# Power.net
KiCad netlist of a schematic drawn in Altium Designer
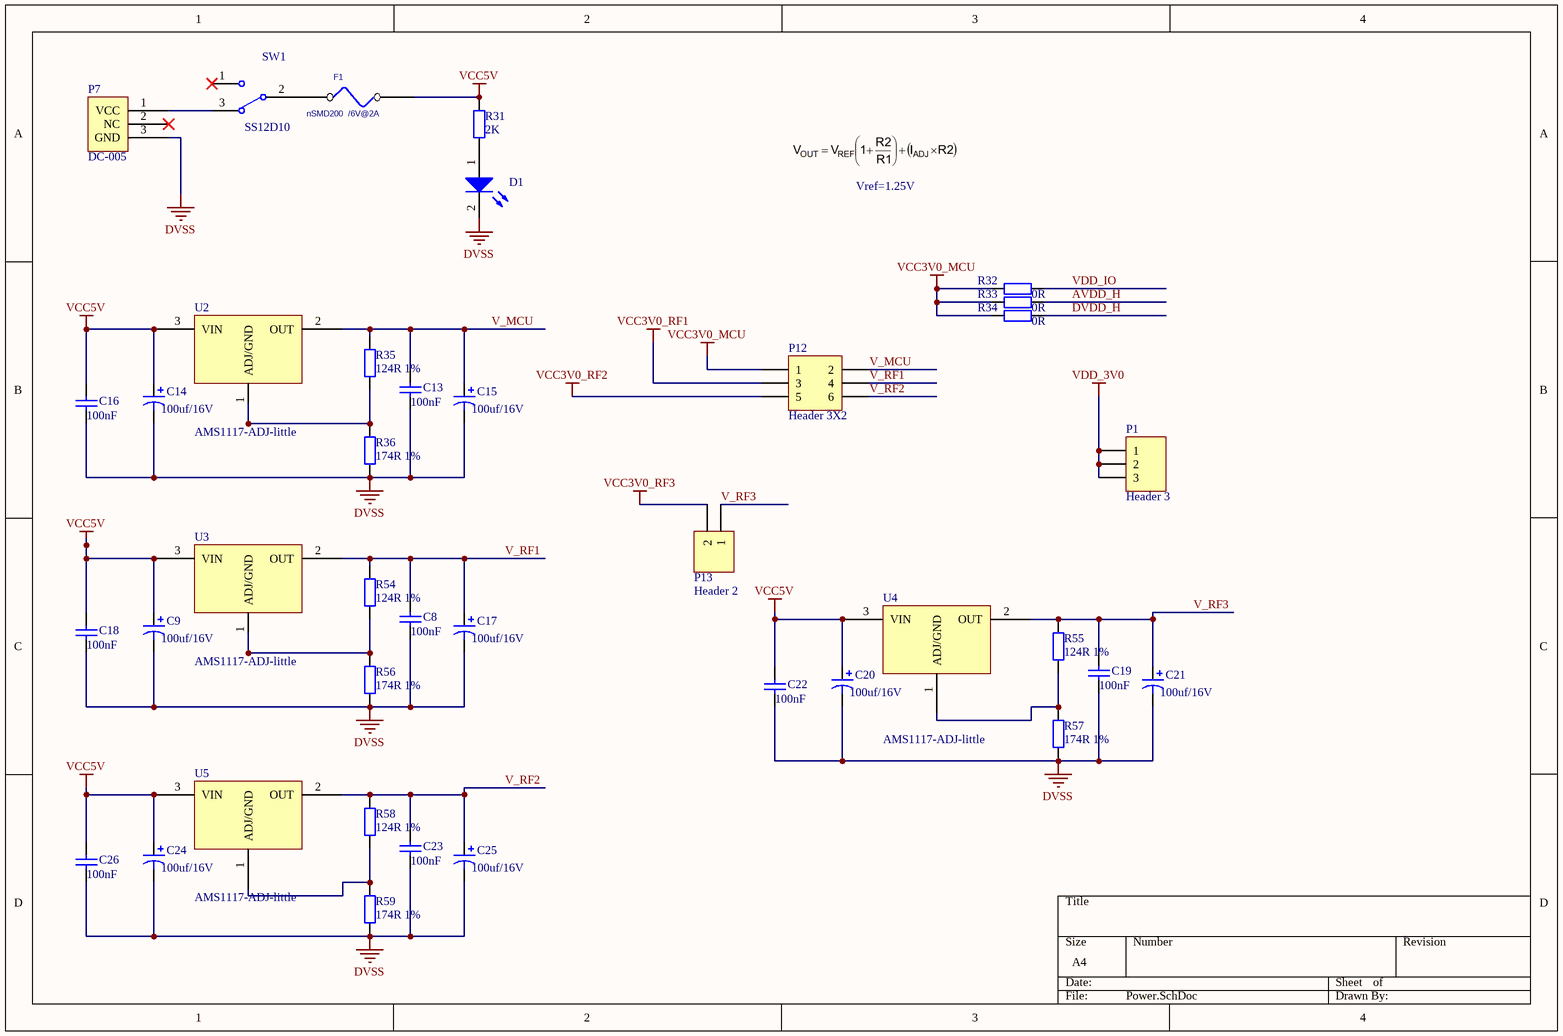
[diagram p0: Power.SchDoc]

(export (version "E")
  (design (tool "Eeschema 10.0.6"))
  (components
    (comp (ref "C8")
      (value "100nF")
      (footprint "R0603")
      (fields (field (name "PUBLISHER") "Altium Limited"))
      (libsource (lib "SKY1311T-READER-V1.0_1") (part "Cap"))
    )
    (comp (ref "C9")
      (value "100uf/16V")
      (footprint "TAN3528")
      (description "tan3528 100uf/16V")
      (fields (field (name "PUBLISHER") "Altium Limited"))
      (libsource (lib "Miscellaneous Devices") (part "Cap Pol1"))
    )
    (comp (ref "C13")
      (value "100nF")
      (footprint "R0603")
      (fields (field (name "PUBLISHER") "Altium Limited"))
      (libsource (lib "SKY1311T-READER-V1.0_1") (part "Cap"))
    )
    (comp (ref "C14")
      (value "100uf/16V")
      (footprint "TAN3528")
      (description "tan3528 100uf/16V")
      (fields (field (name "PUBLISHER") "Altium Limited"))
      (libsource (lib "Miscellaneous Devices") (part "Cap Pol1"))
    )
    (comp (ref "C15")
      (value "100uf/16V")
      (footprint "TAN3528")
      (description "tan3528 100uf/16V")
      (fields (field (name "PUBLISHER") "Altium Limited"))
      (libsource (lib "Miscellaneous Devices") (part "Cap Pol1"))
    )
    (comp (ref "C16")
      (value "100nF")
      (footprint "R0603")
      (fields (field (name "PUBLISHER") "Altium Limited"))
      (libsource (lib "SKY1311T-READER-V1.0_1") (part "Cap"))
    )
    (comp (ref "C17")
      (value "100uf/16V")
      (footprint "TAN3528")
      (description "tan3528 100uf/16V")
      (fields (field (name "PUBLISHER") "Altium Limited"))
      (libsource (lib "Miscellaneous Devices") (part "Cap Pol1"))
    )
    (comp (ref "C18")
      (value "100nF")
      (footprint "R0603")
      (fields (field (name "PUBLISHER") "Altium Limited"))
      (libsource (lib "SKY1311T-READER-V1.0_1") (part "Cap"))
    )
    (comp (ref "C19")
      (value "100nF")
      (footprint "R0603")
      (fields (field (name "PUBLISHER") "Altium Limited"))
      (libsource (lib "SKY1311T-READER-V1.0_1") (part "Cap"))
    )
    (comp (ref "C20")
      (value "100uf/16V")
      (footprint "TAN3528")
      (description "tan3528 100uf/16V")
      (fields (field (name "PUBLISHER") "Altium Limited"))
      (libsource (lib "Miscellaneous Devices") (part "Cap Pol1"))
    )
    (comp (ref "C21")
      (value "100uf/16V")
      (footprint "TAN3528")
      (description "tan3528 100uf/16V")
      (fields (field (name "PUBLISHER") "Altium Limited"))
      (libsource (lib "Miscellaneous Devices") (part "Cap Pol1"))
    )
    (comp (ref "C22")
      (value "100nF")
      (footprint "R0603")
      (fields (field (name "PUBLISHER") "Altium Limited"))
      (libsource (lib "SKY1311T-READER-V1.0_1") (part "Cap"))
    )
    (comp (ref "C23")
      (value "100nF")
      (footprint "R0603")
      (fields (field (name "PUBLISHER") "Altium Limited"))
      (libsource (lib "SKY1311T-READER-V1.0_1") (part "Cap"))
    )
    (comp (ref "C24")
      (value "100uf/16V")
      (footprint "TAN3528")
      (description "tan3528 100uf/16V")
      (fields (field (name "PUBLISHER") "Altium Limited"))
      (libsource (lib "Miscellaneous Devices") (part "Cap Pol1"))
    )
    (comp (ref "C25")
      (value "100uf/16V")
      (footprint "TAN3528")
      (description "tan3528 100uf/16V")
      (fields (field (name "PUBLISHER") "Altium Limited"))
      (libsource (lib "Miscellaneous Devices") (part "Cap Pol1"))
    )
    (comp (ref "C26")
      (value "100nF")
      (footprint "R0603")
      (fields (field (name "PUBLISHER") "Altium Limited"))
      (libsource (lib "SKY1311T-READER-V1.0_1") (part "Cap"))
    )
    (comp (ref "D1")
      (value "LED_Red")
      (footprint "0603d")
      (description "Typical RED, GREEN, YELLOW, AMBER GaAs LED")
      (fields
        (field (name "MANUFACTURER") "Generic Components")
        (field (name "PUBLISHER") "Altium Hobart Technology Centre")
      )
      (libsource (lib "Core_Moudle") (part "LED2"))
    )
    (comp (ref "F1") (value "nSMD200  /6V@2A") (footprint "FN1812") (libsource (lib "*") (part "FUSE")))
    (comp (ref "P1")
      (value "Header 3")
      (footprint "HDR1X3")
      (description "Header, 3-Pin")
      (fields (field (name "PUBLISHER") "Altium Limited"))
      (libsource (lib "Miscellaneous Connectors") (part "Header 3"))
    )
    (comp (ref "P7") (value "DC-005") (footprint "DC005") (libsource (lib "mylib_lyj") (part "DC-005")))
    (comp (ref "P12")
      (value "Header 3X2")
      (footprint "HDR2X3")
      (libsource (lib "SKY32B750_OSPI_EVB1_V2.0") (part "Header 3X2"))
    )
    (comp (ref "P13")
      (value "Header 2")
      (footprint "HDR1X2")
      (description "2.54mm直插针,2P")
      (fields (field (name "PUBLISHER") "Altium Limited"))
      (libsource (lib "Miscellaneous Connectors") (part "Header 2"))
    )
    (comp (ref "R31")
      (value "2K")
      (footprint "R0603")
      (description "Resistor")
      (fields
        (field (name "MANUFACTURER") "Generic Components")
        (field (name "PUBLISHER") "Altium Hobart Technology Centre")
      )
      (libsource (lib "") (part "Res2_1"))
    )
    (comp (ref "R32")
      (value "0R")
      (footprint "R0603")
      (description "Resistor")
      (fields
        (field (name "MANUFACTURER") "Generic Components")
        (field (name "PUBLISHER") "Altium Hobart Technology Centre")
      )
      (libsource (lib "Core_Moudle") (part "Res2"))
    )
    (comp (ref "R33")
      (value "0R")
      (footprint "R0603")
      (description "Resistor")
      (fields
        (field (name "MANUFACTURER") "Generic Components")
        (field (name "PUBLISHER") "Altium Hobart Technology Centre")
      )
      (libsource (lib "Core_Moudle") (part "Res2"))
    )
    (comp (ref "R34")
      (value "0R")
      (footprint "R0603")
      (description "Resistor")
      (fields
        (field (name "MANUFACTURER") "Generic Components")
        (field (name "PUBLISHER") "Altium Hobart Technology Centre")
      )
      (libsource (lib "Core_Moudle") (part "Res2"))
    )
    (comp (ref "R35")
      (value "124R 1%")
      (footprint "R0603")
      (fields (field (name "PUBLISHER") "Altium Limited"))
      (libsource (lib "Miscellaneous Devices") (part "Res2"))
    )
    (comp (ref "R36")
      (value "174R 1%")
      (footprint "R0603")
      (fields (field (name "PUBLISHER") "Altium Limited"))
      (libsource (lib "Miscellaneous Devices") (part "Res2"))
    )
    (comp (ref "R54")
      (value "124R 1%")
      (footprint "R0603")
      (fields (field (name "PUBLISHER") "Altium Limited"))
      (libsource (lib "Miscellaneous Devices") (part "Res2"))
    )
    (comp (ref "R55")
      (value "124R 1%")
      (footprint "R0603")
      (fields (field (name "PUBLISHER") "Altium Limited"))
      (libsource (lib "Miscellaneous Devices") (part "Res2"))
    )
    (comp (ref "R56")
      (value "174R 1%")
      (footprint "R0603")
      (fields (field (name "PUBLISHER") "Altium Limited"))
      (libsource (lib "Miscellaneous Devices") (part "Res2"))
    )
    (comp (ref "R57")
      (value "174R 1%")
      (footprint "R0603")
      (fields (field (name "PUBLISHER") "Altium Limited"))
      (libsource (lib "Miscellaneous Devices") (part "Res2"))
    )
    (comp (ref "R58")
      (value "124R 1%")
      (footprint "R0603")
      (fields (field (name "PUBLISHER") "Altium Limited"))
      (libsource (lib "Miscellaneous Devices") (part "Res2"))
    )
    (comp (ref "R59")
      (value "174R 1%")
      (footprint "R0603")
      (fields (field (name "PUBLISHER") "Altium Limited"))
      (libsource (lib "Miscellaneous Devices") (part "Res2"))
    )
    (comp (ref "SW1") (value "SS12D10") (footprint "SW123") (libsource (lib "jinrylib") (part "SW123")))
    (comp (ref "U2")
      (value "AMS1117-ADJ-little")
      (footprint "LDO-SOT-89-3")
      (description "AMS1117-ADJ-little ,SOT-89-3")
      (libsource (lib "SKY32B750_OSPI_EVB1_V2.0") (part "AMS1117-ADJ-little"))
    )
    (comp (ref "U3")
      (value "AMS1117-ADJ-little")
      (footprint "LDO-SOT-89-3")
      (description "AMS1117-ADJ-little,SOT-89-3")
      (libsource (lib "SKY32B750_OSPI_EVB1_V2.0") (part "AMS1117-ADJ-little"))
    )
    (comp (ref "U4")
      (value "AMS1117-ADJ-little")
      (footprint "LDO-SOT-89-3")
      (description "AMS1117-ADJ-little,SOT-89-3")
      (libsource (lib "SKY32B750_OSPI_EVB1_V2.0") (part "AMS1117-ADJ-little"))
    )
    (comp (ref "U5")
      (value "AMS1117-ADJ-little")
      (footprint "LDO-SOT-89-3")
      (description "AMS1117-ADJ-little,SOT-89-3")
      (libsource (lib "SKY32B750_OSPI_EVB1_V2.0") (part "AMS1117-ADJ-little"))
    )
  )
  (nets
    (net (code "1") (name "/AVDD_H") (class "Default")
      (node (ref "R33") (pin "2") (pinfunction "2_2") (pintype "passive"))
    )
    (net (code "2") (name "/DVDD_H") (class "Default")
      (node (ref "R34") (pin "2") (pinfunction "2_2") (pintype "passive"))
    )
    (net (code "3") (name "/VDD_IO") (class "Default")
      (node (ref "R32") (pin "2") (pinfunction "2_2") (pintype "passive"))
    )
    (net (code "4") (name "/V_MCU") (class "Default")
      (node (ref "C13") (pin "2") (pinfunction "2_2") (pintype "passive"))
      (node (ref "C15") (pin "1") (pinfunction "1_1") (pintype "passive"))
      (node (ref "P12") (pin "2") (pinfunction "2_2") (pintype "passive"))
      (node (ref "R35") (pin "2") (pinfunction "2_2") (pintype "passive"))
      (node (ref "U2") (pin "2") (pinfunction "OUT_2") (pintype "passive"))
    )
    (net (code "5") (name "/V_RF1") (class "Default")
      (node (ref "C17") (pin "1") (pinfunction "1_1") (pintype "passive"))
      (node (ref "C8") (pin "2") (pinfunction "2_2") (pintype "passive"))
      (node (ref "P12") (pin "4") (pinfunction "4_4") (pintype "passive"))
      (node (ref "R54") (pin "2") (pinfunction "2_2") (pintype "passive"))
      (node (ref "U3") (pin "2") (pinfunction "OUT_2") (pintype "passive"))
    )
    (net (code "6") (name "/V_RF2") (class "Default")
      (node (ref "C23") (pin "2") (pinfunction "2_2") (pintype "passive"))
      (node (ref "C25") (pin "1") (pinfunction "1_1") (pintype "passive"))
      (node (ref "P12") (pin "6") (pinfunction "6_6") (pintype "passive"))
      (node (ref "R58") (pin "2") (pinfunction "2_2") (pintype "passive"))
      (node (ref "U5") (pin "2") (pinfunction "OUT_2") (pintype "passive"))
    )
    (net (code "7") (name "/V_RF3") (class "Default")
      (node (ref "C19") (pin "2") (pinfunction "2_2") (pintype "passive"))
      (node (ref "C21") (pin "1") (pinfunction "1_1") (pintype "passive"))
      (node (ref "P13") (pin "1") (pinfunction "1_1") (pintype "passive"))
      (node (ref "R55") (pin "2") (pinfunction "2_2") (pintype "passive"))
      (node (ref "U4") (pin "2") (pinfunction "OUT_2") (pintype "passive"))
    )
    (net (code "8") (name "DVSS") (class "Default")
      (node (ref "C13") (pin "1") (pinfunction "1_1") (pintype "passive"))
      (node (ref "C14") (pin "2") (pinfunction "2_2") (pintype "passive"))
      (node (ref "C15") (pin "2") (pinfunction "2_2") (pintype "passive"))
      (node (ref "C16") (pin "1") (pinfunction "1_1") (pintype "passive"))
      (node (ref "C17") (pin "2") (pinfunction "2_2") (pintype "passive"))
      (node (ref "C18") (pin "1") (pinfunction "1_1") (pintype "passive"))
      (node (ref "C19") (pin "1") (pinfunction "1_1") (pintype "passive"))
      (node (ref "C20") (pin "2") (pinfunction "2_2") (pintype "passive"))
      (node (ref "C21") (pin "2") (pinfunction "2_2") (pintype "passive"))
      (node (ref "C22") (pin "1") (pinfunction "1_1") (pintype "passive"))
      (node (ref "C23") (pin "1") (pinfunction "1_1") (pintype "passive"))
      (node (ref "C24") (pin "2") (pinfunction "2_2") (pintype "passive"))
      (node (ref "C25") (pin "2") (pinfunction "2_2") (pintype "passive"))
      (node (ref "C26") (pin "1") (pinfunction "1_1") (pintype "passive"))
      (node (ref "C8") (pin "1") (pinfunction "1_1") (pintype "passive"))
      (node (ref "C9") (pin "2") (pinfunction "2_2") (pintype "passive"))
      (node (ref "D1") (pin "2") (pinfunction "K_2") (pintype "passive"))
      (node (ref "P7") (pin "3") (pinfunction "GND_3") (pintype "passive"))
      (node (ref "R36") (pin "1") (pinfunction "1_1") (pintype "passive"))
      (node (ref "R56") (pin "1") (pinfunction "1_1") (pintype "passive"))
      (node (ref "R57") (pin "1") (pinfunction "1_1") (pintype "passive"))
      (node (ref "R59") (pin "1") (pinfunction "1_1") (pintype "passive"))
    )
    (net (code "9") (name "Net-(D1-A)") (class "Default")
      (node (ref "D1") (pin "1") (pinfunction "A_1") (pintype "passive"))
      (node (ref "R31") (pin "2") (pinfunction "2_2") (pintype "passive"))
    )
    (net (code "10") (name "Net-(F1-Pad1)") (class "Default")
      (node (ref "F1") (pin "1") (pinfunction "1_1") (pintype "passive"))
      (node (ref "SW1") (pin "2") (pinfunction "2_2") (pintype "passive"))
    )
    (net (code "11") (name "Net-(P7-VCC)") (class "Default")
      (node (ref "P7") (pin "1") (pinfunction "VCC_1") (pintype "passive"))
      (node (ref "SW1") (pin "3") (pinfunction "3_3") (pintype "passive"))
    )
    (net (code "12") (name "Net-(U2-ADJ{slash}GND)") (class "Default")
      (node (ref "R35") (pin "1") (pinfunction "1_1") (pintype "passive"))
      (node (ref "R36") (pin "2") (pinfunction "2_2") (pintype "passive"))
      (node (ref "U2") (pin "1") (pinfunction "ADJ/GND_1") (pintype "passive"))
    )
    (net (code "13") (name "Net-(U3-ADJ{slash}GND)") (class "Default")
      (node (ref "R54") (pin "1") (pinfunction "1_1") (pintype "passive"))
      (node (ref "R56") (pin "2") (pinfunction "2_2") (pintype "passive"))
      (node (ref "U3") (pin "1") (pinfunction "ADJ/GND_1") (pintype "passive"))
    )
    (net (code "14") (name "Net-(U4-ADJ{slash}GND)") (class "Default")
      (node (ref "R55") (pin "1") (pinfunction "1_1") (pintype "passive"))
      (node (ref "R57") (pin "2") (pinfunction "2_2") (pintype "passive"))
      (node (ref "U4") (pin "1") (pinfunction "ADJ/GND_1") (pintype "passive"))
    )
    (net (code "15") (name "Net-(U5-ADJ{slash}GND)") (class "Default")
      (node (ref "R58") (pin "1") (pinfunction "1_1") (pintype "passive"))
      (node (ref "R59") (pin "2") (pinfunction "2_2") (pintype "passive"))
      (node (ref "U5") (pin "1") (pinfunction "ADJ/GND_1") (pintype "passive"))
    )
    (net (code "16") (name "VCC3V0_MCU") (class "Default")
      (node (ref "P12") (pin "1") (pinfunction "1_1") (pintype "passive"))
      (node (ref "R32") (pin "1") (pinfunction "1_1") (pintype "passive"))
      (node (ref "R33") (pin "1") (pinfunction "1_1") (pintype "passive"))
      (node (ref "R34") (pin "1") (pinfunction "1_1") (pintype "passive"))
    )
    (net (code "17") (name "VCC3V0_RF1") (class "Default")
      (node (ref "P12") (pin "3") (pinfunction "3_3") (pintype "passive"))
    )
    (net (code "18") (name "VCC3V0_RF2") (class "Default")
      (node (ref "P12") (pin "5") (pinfunction "5_5") (pintype "passive"))
    )
    (net (code "19") (name "VCC3V0_RF3") (class "Default")
      (node (ref "P13") (pin "2") (pinfunction "2_2") (pintype "passive"))
    )
    (net (code "20") (name "VCC5V") (class "Default")
      (node (ref "C14") (pin "1") (pinfunction "1_1") (pintype "passive"))
      (node (ref "C16") (pin "2") (pinfunction "2_2") (pintype "passive"))
      (node (ref "C18") (pin "2") (pinfunction "2_2") (pintype "passive"))
      (node (ref "C20") (pin "1") (pinfunction "1_1") (pintype "passive"))
      (node (ref "C22") (pin "2") (pinfunction "2_2") (pintype "passive"))
      (node (ref "C24") (pin "1") (pinfunction "1_1") (pintype "passive"))
      (node (ref "C26") (pin "2") (pinfunction "2_2") (pintype "passive"))
      (node (ref "C9") (pin "1") (pinfunction "1_1") (pintype "passive"))
      (node (ref "F1") (pin "2") (pinfunction "2_2") (pintype "passive"))
      (node (ref "R31") (pin "1") (pinfunction "1_1") (pintype "passive"))
      (node (ref "U2") (pin "3") (pinfunction "VIN_3") (pintype "passive"))
      (node (ref "U3") (pin "3") (pinfunction "VIN_3") (pintype "passive"))
      (node (ref "U4") (pin "3") (pinfunction "VIN_3") (pintype "passive"))
      (node (ref "U5") (pin "3") (pinfunction "VIN_3") (pintype "passive"))
    )
    (net (code "21") (name "VDD_3V0") (class "Default")
      (node (ref "P1") (pin "1") (pinfunction "1_1") (pintype "passive"))
      (node (ref "P1") (pin "2") (pinfunction "2_2") (pintype "passive"))
      (node (ref "P1") (pin "3") (pinfunction "3_3") (pintype "passive"))
    )
    (net (code "22") (name "unconnected-(P7-NC-Pad2)") (class "Default")
      (node (ref "P7") (pin "2") (pinfunction "NC_2") (pintype "passive+no_connect"))
    )
    (net (code "23") (name "unconnected-(SW1-Pad1)") (class "Default")
      (node (ref "SW1") (pin "1") (pinfunction "1_1") (pintype "passive+no_connect"))
    )
  )
)
